# TopLevel.net
KiCad netlist of a schematic drawn in Altium Designer
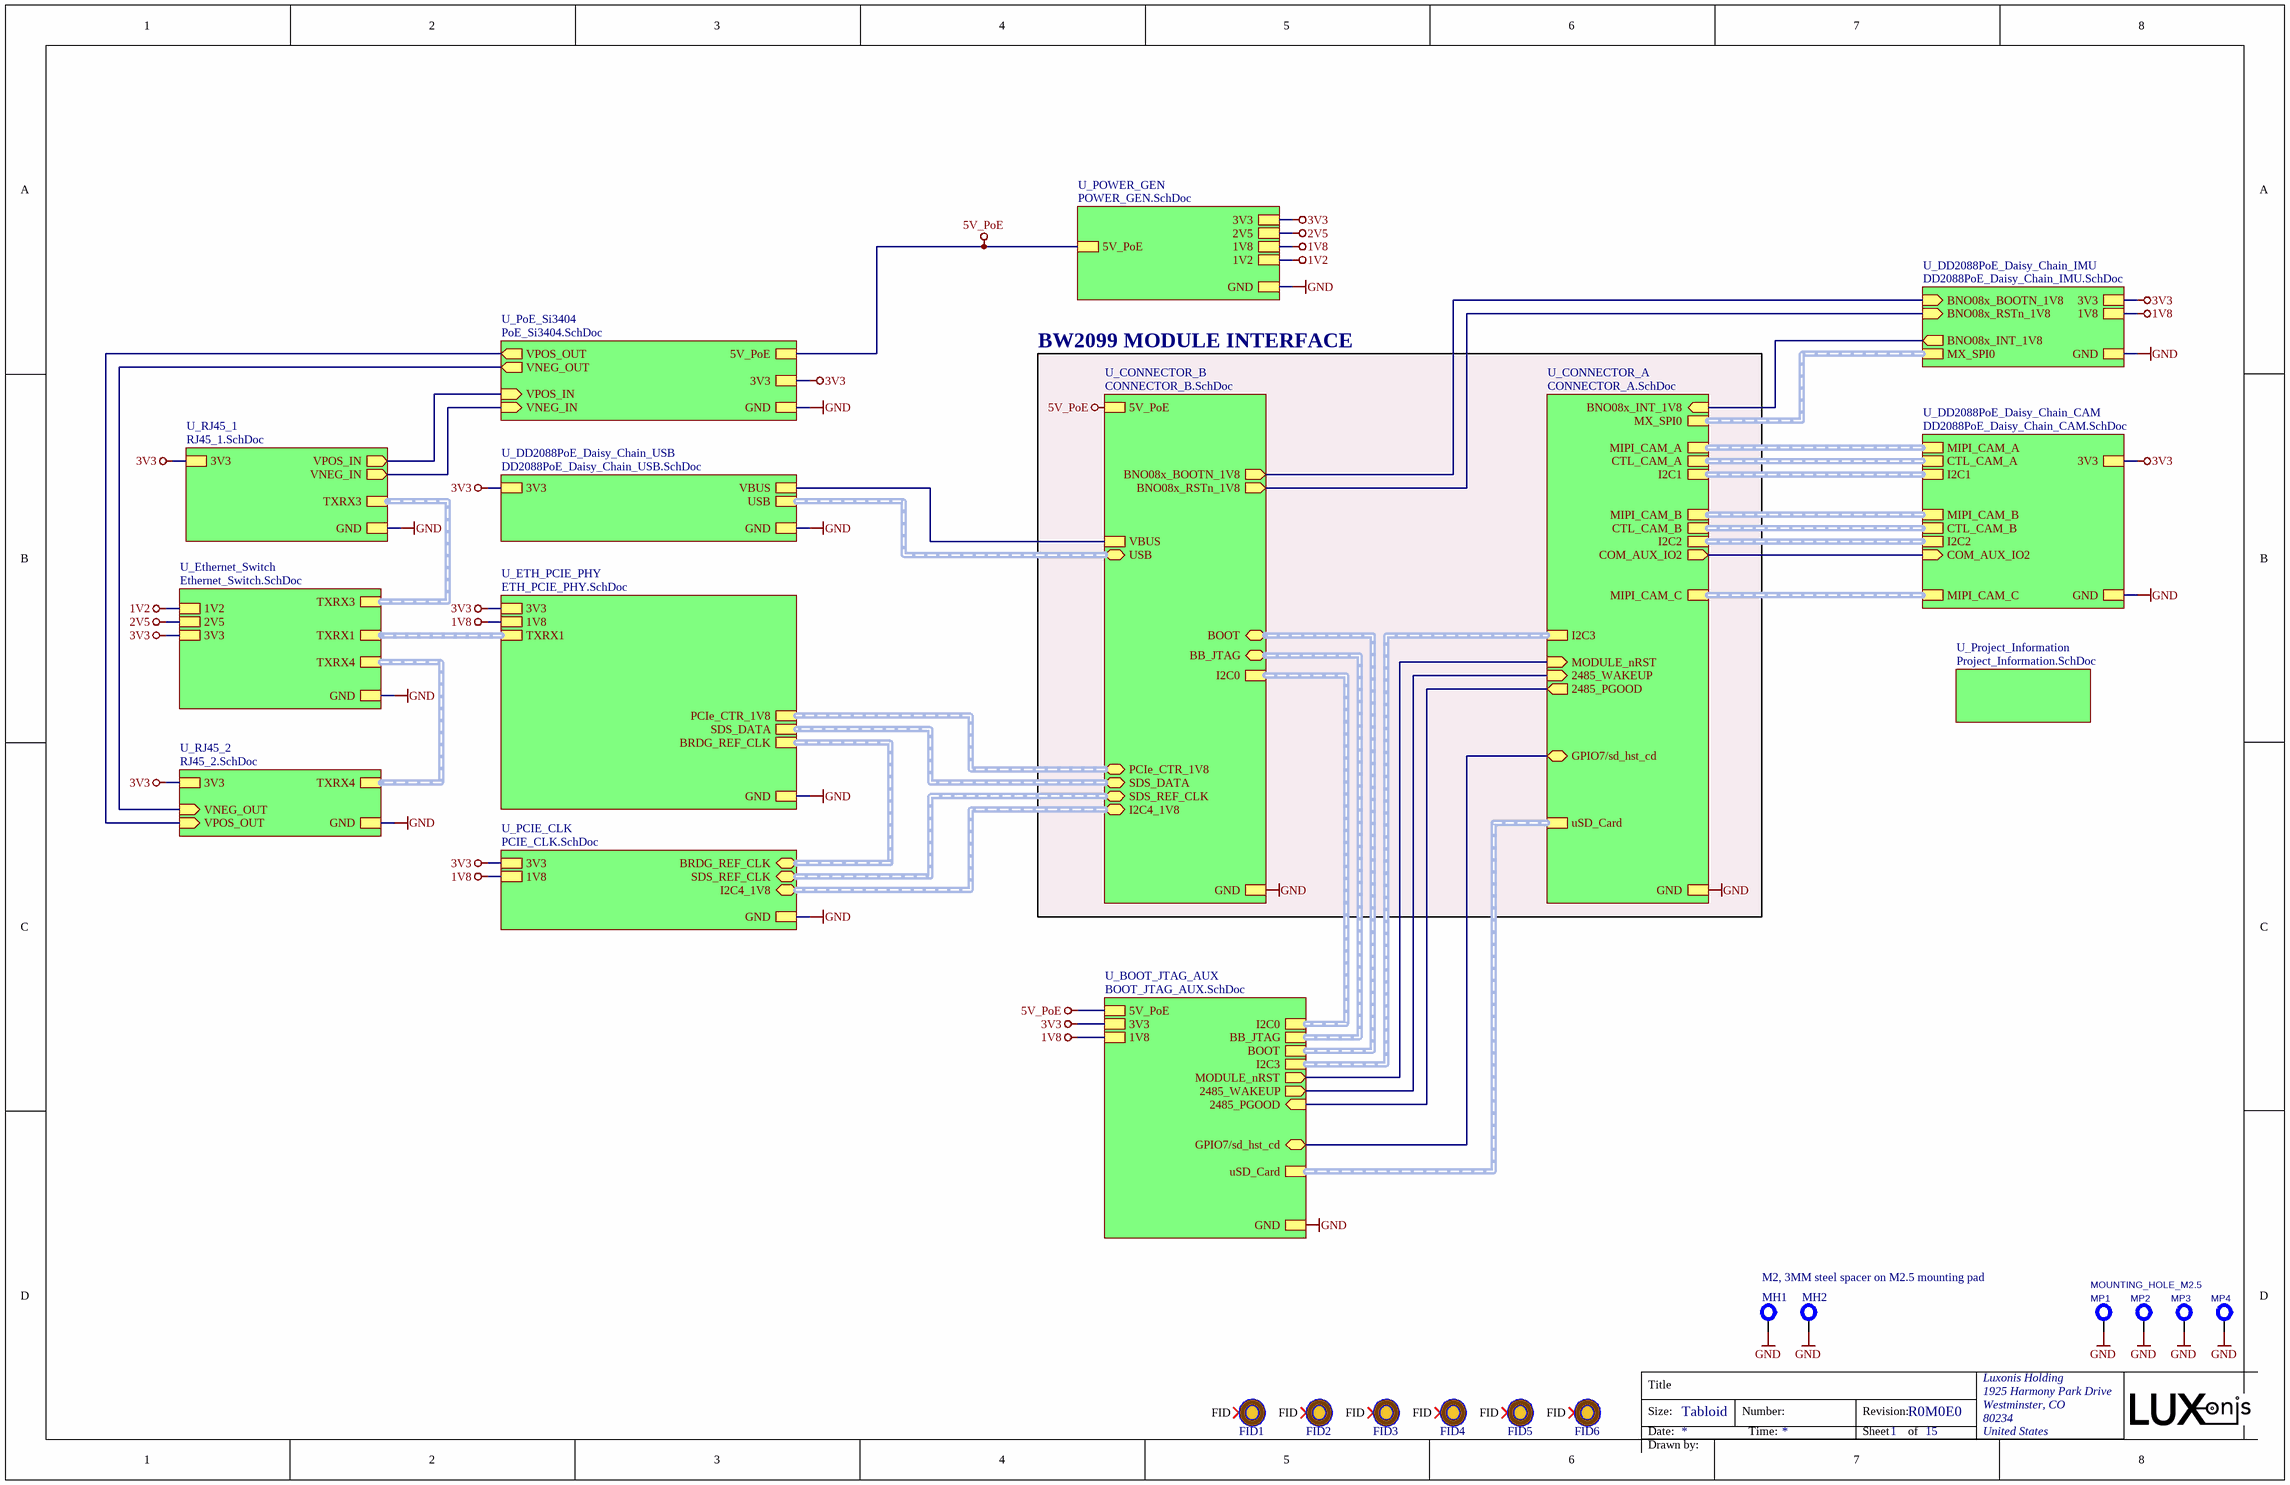
[diagram p0: TopLevel.SchDoc]

(export (version "E")
  (design (tool "Eeschema 10.0.6"))
  (components
    (comp (ref "FID1")
      (value "FIDUCIAL_ROUND_1MM")
      (footprint "LuxonisMaster:FIDUCIAL_ROUND_1MM")
      (description "Fiducial with various available footprints")
      (libsource (lib "LuxonisMaster") (part "FIDUCIAL"))
    )
    (comp (ref "FID2")
      (value "FIDUCIAL_ROUND_1MM")
      (footprint "LuxonisMaster:FIDUCIAL_ROUND_1MM")
      (description "Fiducial with various available footprints")
      (libsource (lib "LuxonisMaster") (part "FIDUCIAL"))
    )
    (comp (ref "FID3")
      (value "FIDUCIAL_ROUND_1MM")
      (footprint "LuxonisMaster:FIDUCIAL_ROUND_1MM")
      (description "Fiducial with various available footprints")
      (libsource (lib "LuxonisMaster") (part "FIDUCIAL"))
    )
    (comp (ref "FID4")
      (value "FIDUCIAL_ROUND_1MM")
      (footprint "LuxonisMaster:FIDUCIAL_ROUND_1MM")
      (description "Fiducial with various available footprints")
      (libsource (lib "LuxonisMaster") (part "FIDUCIAL"))
    )
    (comp (ref "FID5")
      (value "FIDUCIAL_ROUND_1MM")
      (footprint "LuxonisMaster:FIDUCIAL_ROUND_1MM")
      (description "Fiducial with various available footprints")
      (libsource (lib "LuxonisMaster") (part "FIDUCIAL"))
    )
    (comp (ref "FID6")
      (value "FIDUCIAL_ROUND_1MM")
      (footprint "LuxonisMaster:FIDUCIAL_ROUND_1MM")
      (description "Fiducial with various available footprints")
      (libsource (lib "LuxonisMaster") (part "FIDUCIAL"))
    )
    (comp (ref "MH1")
      (value "M2, 3MM steel spacer on M2.5 mounting pad")
      (footprint "LuxonisMaster:9774030243R")
      (description "MP ROUND STANDOFF M2X0.4 STEEL 3MM")
      (libsource (lib "LuxonisMaster") (part "9774030243R"))
    )
    (comp (ref "MH2")
      (value "M2, 3MM steel spacer on M2.5 mounting pad")
      (footprint "LuxonisMaster:9774030243R")
      (description "MP ROUND STANDOFF M2X0.4 STEEL 3MM")
      (libsource (lib "LuxonisMaster") (part "9774030243R"))
    )
    (comp (ref "MP1")
      (value "MOUNTING_HOLE_M2.5")
      (footprint "LuxonisMaster:MOUNTING_HOLE_M2.5")
      (description "=CurrentFootprint")
      (libsource (lib "LuxonisMaster") (part "MP_Mounting-Holes"))
    )
    (comp (ref "MP2")
      (value "MOUNTING_HOLE_M2.5")
      (footprint "LuxonisMaster:MOUNTING_HOLE_M2.5")
      (description "=CurrentFootprint")
      (libsource (lib "LuxonisMaster") (part "MP_Mounting-Holes"))
    )
    (comp (ref "MP3")
      (value "MOUNTING_HOLE_M2.5")
      (footprint "LuxonisMaster:MOUNTING_HOLE_M2.5")
      (description "=CurrentFootprint")
      (libsource (lib "LuxonisMaster") (part "MP_Mounting-Holes"))
    )
    (comp (ref "MP4")
      (value "MOUNTING_HOLE_M2.5")
      (footprint "LuxonisMaster:MOUNTING_HOLE_M2.5")
      (description "=CurrentFootprint")
      (libsource (lib "LuxonisMaster") (part "MP_Mounting-Holes"))
    )
  )
  (nets
    (net (code "41") (name "GND") (class "Default")
      (node (ref "MH1") (pin "1") (pintype "passive"))
      (node (ref "MH2") (pin "1") (pintype "passive"))
      (node (ref "MP1") (pin "1") (pintype "passive"))
      (node (ref "MP2") (pin "1") (pintype "passive"))
      (node (ref "MP3") (pin "1") (pintype "passive"))
      (node (ref "MP4") (pin "1") (pintype "passive"))
    )
    (net (code "42") (name "unconnected-(FID1-PadFID)") (class "Default")
      (node (ref "FID1") (pin "FID") (pinfunction "FID_FID") (pintype "input+no_connect"))
    )
    (net (code "43") (name "unconnected-(FID2-PadFID)") (class "Default")
      (node (ref "FID2") (pin "FID") (pinfunction "FID_FID") (pintype "input+no_connect"))
    )
    (net (code "44") (name "unconnected-(FID3-PadFID)") (class "Default")
      (node (ref "FID3") (pin "FID") (pinfunction "FID_FID") (pintype "input+no_connect"))
    )
    (net (code "45") (name "unconnected-(FID4-PadFID)") (class "Default")
      (node (ref "FID4") (pin "FID") (pinfunction "FID_FID") (pintype "input+no_connect"))
    )
    (net (code "46") (name "unconnected-(FID5-PadFID)") (class "Default")
      (node (ref "FID5") (pin "FID") (pinfunction "FID_FID") (pintype "input+no_connect"))
    )
    (net (code "47") (name "unconnected-(FID6-PadFID)") (class "Default")
      (node (ref "FID6") (pin "FID") (pinfunction "FID_FID") (pintype "input+no_connect"))
    )
  )
)
